# Main.net
KiCad netlist of a schematic drawn in Altium Designer
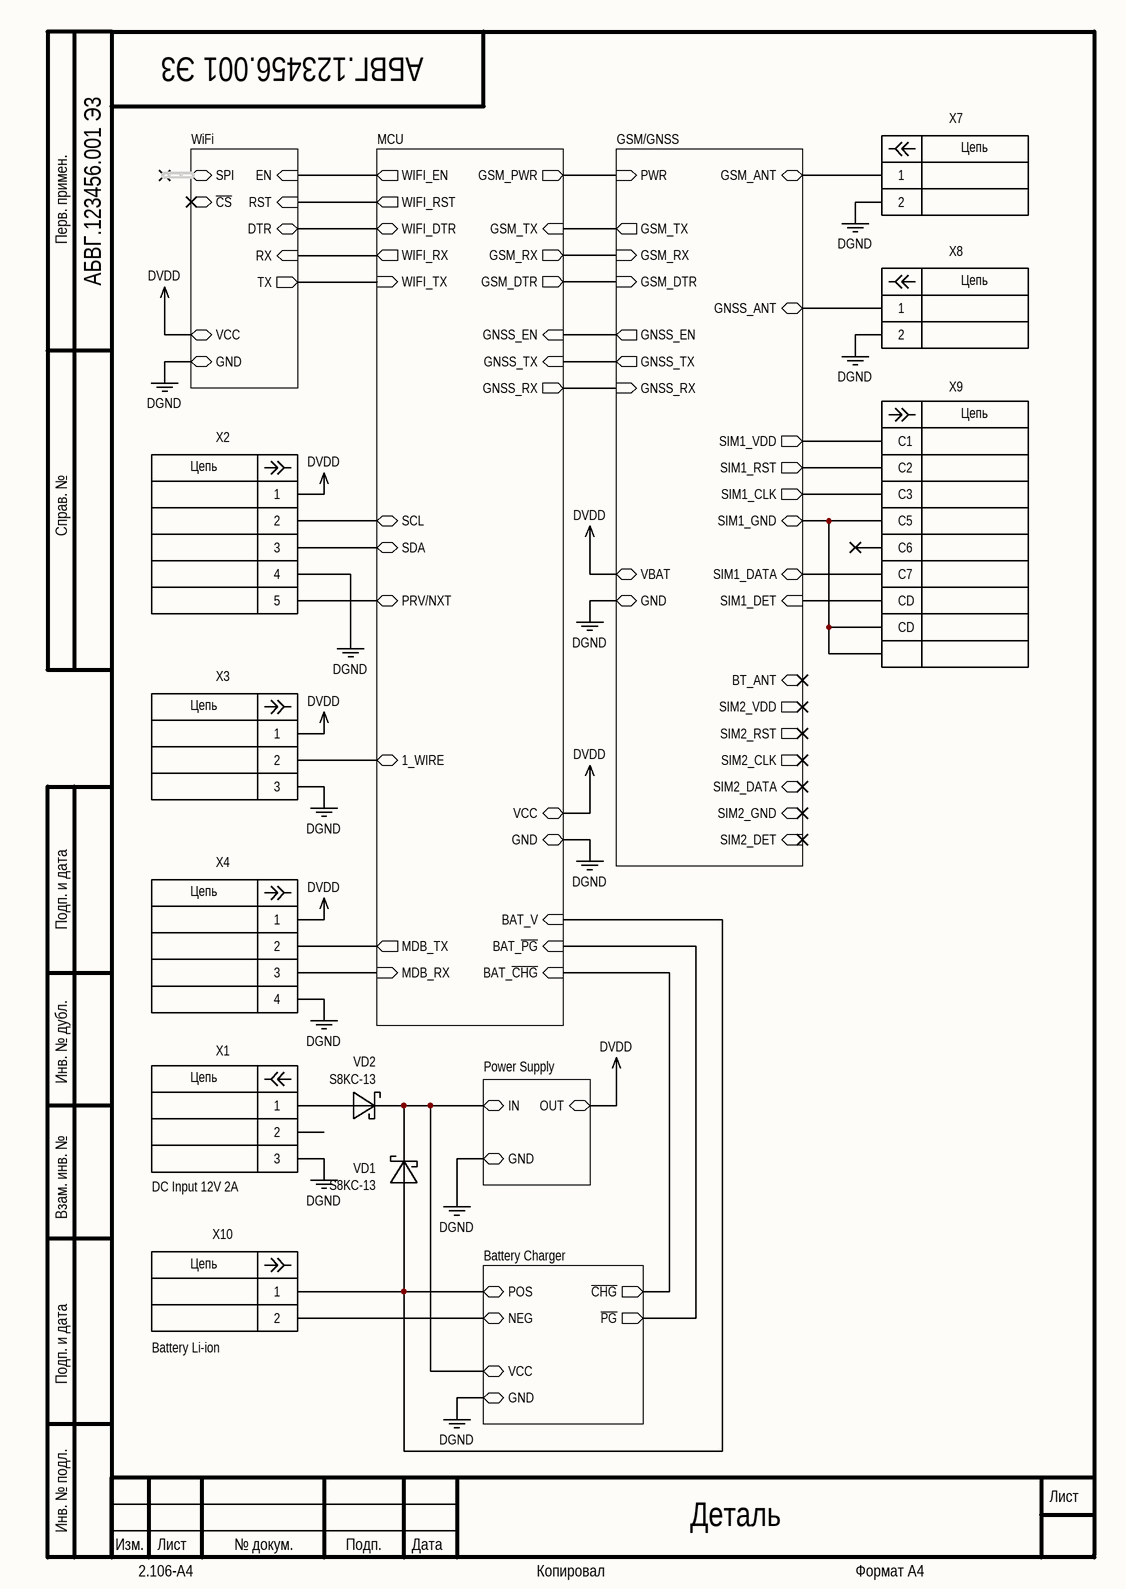
[diagram p0: Main.SchDoc]

(export (version "E")
  (design (tool "Eeschema 10.0.6"))
  (components
    (comp (ref "VD1")
      (value "S8KC-13")
      (footprint "DO-214AB")
      (description "Diode Schottky 8A 800V")
      (fields (field (name "MANUFACTURER") "ON Semiconductor"))
      (libsource (lib "Discrete components") (part "S8KC-13"))
    )
    (comp (ref "VD2")
      (value "S8KC-13")
      (footprint "DO-214AB")
      (description "Diode Schottky 8A 800V")
      (fields (field (name "MANUFACTURER") "ON Semiconductor"))
      (libsource (lib "Discrete components") (part "S8KC-13"))
    )
    (comp (ref "X1")
      (value "PJ-002A")
      (footprint "PJ-002A")
      (description "Power Jack, DC")
      (fields (field (name "MANUFACTURER") "CUI"))
      (libsource (lib "Connectors") (part "PJ-002A"))
    )
    (comp (ref "X2")
      (value "S5B-XH-A")
      (footprint "S5B-XH-A")
      (description "Header 2.54 5p Right")
      (fields (field (name "MANUFACTURER") "JST Sales America Inc"))
      (libsource (lib "Connectors") (part "S5B-XH-A"))
    )
    (comp (ref "X3")
      (value "S3B-XH-A")
      (footprint "S3B-XH-A")
      (description "Header, 2.54, 3p, Right")
      (fields (field (name "MANUFACTURER") "JST Sales America Inc"))
      (libsource (lib "Connectors") (part "S3B-XH-A"))
    )
    (comp (ref "X4")
      (value "*")
      (footprint "S4B-XH-A")
      (description "Header 2.54 4p Right")
      (fields (field (name "MANUFACTURER") "JST Sales America Inc"))
      (libsource (lib "Connectors") (part "S4B-XH-A"))
    )
    (comp (ref "X7")
      (value "HYR-1141")
      (footprint "HYR-1141")
      (description "SMA Jack, TH Right")
      (fields (field (name "MANUFACTURER") "HOYUTEC"))
      (libsource (lib "Connectors") (part "HYR-1141"))
    )
    (comp (ref "X8")
      (value "HYR-1141")
      (footprint "HYR-1141")
      (description "SMA Jack, TH Right")
      (fields (field (name "MANUFACTURER") "HOYUTEC"))
      (libsource (lib "Connectors") (part "HYR-1141"))
    )
    (comp (ref "X9")
      (value "47553-0001")
      (footprint "47553-0001")
      (description "SIM card connector")
      (fields (field (name "MANUFACTURER") "Molex"))
      (libsource (lib "Connectors") (part "47553-0001"))
    )
    (comp (ref "X10")
      (value "*")
      (footprint "B2B-XH-A")
      (description "Header, 2.54, 2p, Top")
      (fields (field (name "MANUFACTURER") "JST Sales America Inc"))
      (libsource (lib "Connectors") (part "B2B-XH-A"))
    )
  )
  (nets
    (net (code "1") (name "/1_WIRE") (class "Default")
      (node (ref "X3") (pin "2") (pinfunction "2_2") (pintype "passive"))
    )
    (net (code "2") (name "/BAT_V") (class "Default")
      (node (ref "VD1") (pin "1") (pinfunction "Anode_1") (pintype "passive"))
      (node (ref "X10") (pin "1") (pinfunction "1_1") (pintype "passive"))
    )
    (net (code "5") (name "/GNSS_ANT") (class "Default")
      (node (ref "X8") (pin "1") (pinfunction "1_1") (pintype "passive"))
    )
    (net (code "9") (name "/GSM_ANT") (class "Default")
      (node (ref "X7") (pin "1") (pinfunction "1_1") (pintype "passive"))
    )
    (net (code "14") (name "/IN") (class "Default")
      (node (ref "VD1") (pin "2") (pinfunction "Cathode_2") (pintype "passive"))
      (node (ref "VD2") (pin "2") (pinfunction "Cathode_2") (pintype "passive"))
    )
    (net (code "15") (name "/MDB_RX") (class "Default")
      (node (ref "X4") (pin "3") (pinfunction "3_3") (pintype "passive"))
    )
    (net (code "16") (name "/MDB_TX") (class "Default")
      (node (ref "X4") (pin "2") (pinfunction "2_2") (pintype "passive"))
    )
    (net (code "17") (name "/NEG") (class "Default")
      (node (ref "X10") (pin "2") (pinfunction "2_2") (pintype "passive"))
    )
    (net (code "18") (name "/PRV{slash}NXT") (class "Default")
      (node (ref "X2") (pin "5") (pinfunction "5_5") (pintype "passive"))
    )
    (net (code "19") (name "/SCL") (class "Default")
      (node (ref "X2") (pin "2") (pinfunction "2_2") (pintype "passive"))
    )
    (net (code "20") (name "/SDA") (class "Default")
      (node (ref "X2") (pin "3") (pinfunction "3_3") (pintype "passive"))
    )
    (net (code "21") (name "/SIM1_CLK") (class "Default")
      (node (ref "X9") (pin "C3") (pinfunction "C3_C3") (pintype "passive"))
    )
    (net (code "22") (name "/SIM1_DATA") (class "Default")
      (node (ref "X9") (pin "C7") (pinfunction "C7_C7") (pintype "passive"))
    )
    (net (code "23") (name "/SIM1_DET") (class "Default")
      (node (ref "X9") (pin "CD1") (pinfunction "CD_CD1") (pintype "passive"))
    )
    (net (code "24") (name "/SIM1_GND") (class "Default")
      (node (ref "X9") (pin "C5") (pinfunction "C5_C5") (pintype "passive"))
      (node (ref "X9") (pin "CASE") (pinfunction "CASE_CASE") (pintype "passive"))
      (node (ref "X9") (pin "CD2") (pinfunction "CD_CD2") (pintype "passive"))
    )
    (net (code "25") (name "/SIM1_RST") (class "Default")
      (node (ref "X9") (pin "C2") (pinfunction "C2_C2") (pintype "passive"))
    )
    (net (code "26") (name "/SIM1_VDD") (class "Default")
      (node (ref "X9") (pin "C1") (pinfunction "C1_C1") (pintype "passive"))
    )
    (net (code "41") (name "DGND") (class "Default")
      (node (ref "X1") (pin "3") (pinfunction "3_3") (pintype "passive"))
      (node (ref "X2") (pin "4") (pinfunction "4_4") (pintype "passive"))
      (node (ref "X3") (pin "3") (pinfunction "3_3") (pintype "passive"))
      (node (ref "X4") (pin "4") (pinfunction "4_4") (pintype "passive"))
      (node (ref "X7") (pin "2") (pinfunction "2_2") (pintype "passive"))
      (node (ref "X8") (pin "2") (pinfunction "2_2") (pintype "passive"))
    )
    (net (code "42") (name "DVDD") (class "Default")
      (node (ref "X2") (pin "1") (pinfunction "1_1") (pintype "passive"))
      (node (ref "X3") (pin "1") (pinfunction "1_1") (pintype "passive"))
      (node (ref "X4") (pin "1") (pinfunction "1_1") (pintype "passive"))
    )
    (net (code "43") (name "Net-(VD2-Anode)") (class "Default")
      (node (ref "VD2") (pin "1") (pinfunction "Anode_1") (pintype "passive"))
      (node (ref "X1") (pin "1") (pinfunction "1_1") (pintype "passive"))
    )
    (net (code "44") (name "unconnected-(X1-Pad2)") (class "Default")
      (node (ref "X1") (pin "2") (pinfunction "2_2") (pintype "passive"))
    )
    (net (code "45") (name "unconnected-(X9-PadC6)") (class "Default")
      (node (ref "X9") (pin "C6") (pinfunction "C6_C6") (pintype "passive+no_connect"))
    )
  )
)
